# MP2359_ADJ_StepDown100mA.net
KiCad netlist of a schematic drawn in Altium Designer
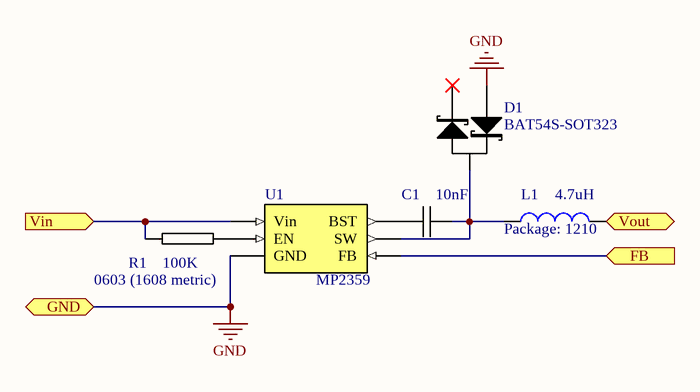
[diagram p0: MP2359_ADJ_StepDown100mA.SchDoc]

(export (version "E")
  (design (tool "Eeschema 10.0.6"))
  (components
    (comp (ref "C1")
      (value "10nF")
      (footprint "0603C-GENERIC")
      (description "CAPACITOR 0603 CERAMIC")
      (fields
        (field (name "MANUFACTURER PART NUMBER") "GRM188R71H103KA01D")
        (field (name "MANUFACTURER") "Murata Electronics North America")
      )
      (libsource (lib "vh_altium_library") (part "0603C-10NF-50V-X7R-MUR"))
    )
    (comp (ref "D1")
      (value "BAT54S-SOT323")
      (footprint "SOT323-123")
      (description "DUAL SCHOTTKY DIODE SERIES")
      (fields
        (field (name "MANUFACTURER") "NXP Semiconductors")
        (field (name "MANUFACTURER PART NUMBER") "BAT54SW,115")
      )
      (libsource (lib "vh_altium_library") (part "BAT54S-SOT323"))
    )
    (comp (ref "L1")
      (value "IND")
      (footprint "C_1210")
      (fields (field (name "INDUCTANCE") "4.7uH") (field (name "PACKAGE") "1210"))
      (libsource (lib "MyLibAltium_v1") (part "Inductor"))
    )
    (comp (ref "R1")
      (value "100K")
      (footprint "0603R-100K")
      (description "GENERIC RESISTOR 0603")
      (fields
        (field (name "TOLERANCE") "±1%")
        (field (name "MANUFACTURER PART NUMBER") "RMCF 1/16 100K 1% R")
        (field (name "CASE") "0603 (1608 metric)")
      )
      (libsource (lib "vh_altium_library") (part "0603R-100K"))
    )
    (comp (ref "U1")
      (value "MP2359")
      (footprint "TSOP23-6")
      (description "monolithic step-down switch  mode converter with a built-in power MOSFET")
      (libsource (lib "MyLibAltium_v1") (part "MP2359"))
    )
  )
  (nets
    (net (code "1") (name "/FB") (class "Default")
      (node (ref "U1") (pin "3") (pinfunction "FB_3") (pintype "input"))
    )
    (net (code "2") (name "/Vin") (class "Default")
      (node (ref "R1") (pin "1") (pintype "passive"))
      (node (ref "U1") (pin "5") (pinfunction "Vin_5") (pintype "input"))
    )
    (net (code "3") (name "/Vout") (class "Default")
      (node (ref "L1") (pin "2") (pinfunction "2_2") (pintype "passive"))
    )
    (net (code "4") (name "GND") (class "Default")
      (node (ref "D1") (pin "1") (pinfunction "1_1") (pintype "passive"))
      (node (ref "U1") (pin "2") (pinfunction "GND_2") (pintype "power_in"))
    )
    (net (code "5") (name "Net-(U1-BST)") (class "Default")
      (node (ref "C1") (pin "1") (pintype "passive"))
      (node (ref "U1") (pin "1") (pinfunction "BST_1") (pintype "output"))
    )
    (net (code "6") (name "Net-(U1-EN)") (class "Default")
      (node (ref "R1") (pin "2") (pintype "passive"))
      (node (ref "U1") (pin "4") (pinfunction "EN_4") (pintype "input"))
    )
    (net (code "7") (name "Net-(U1-SW)") (class "Default")
      (node (ref "C1") (pin "2") (pintype "passive"))
      (node (ref "D1") (pin "3") (pinfunction "3_3") (pintype "passive"))
      (node (ref "L1") (pin "1") (pinfunction "1_1") (pintype "passive"))
      (node (ref "U1") (pin "6") (pinfunction "SW_6") (pintype "output"))
    )
    (net (code "8") (name "unconnected-(D1-Pad2)") (class "Default")
      (node (ref "D1") (pin "2") (pinfunction "2_2") (pintype "passive+no_connect"))
    )
  )
)
